# Tracker_RS232_2.net
KiCad netlist of a schematic drawn in Altium Designer
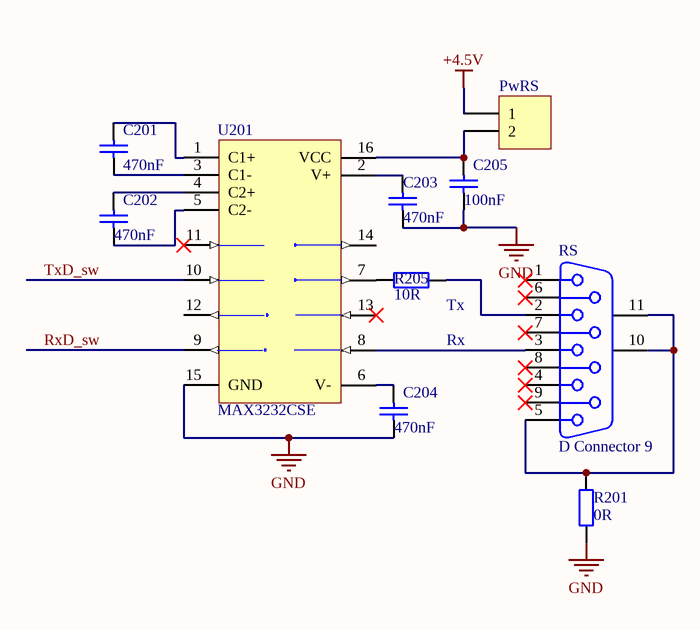
[diagram p0: Tracker RS232_2.SchDoc]

(export (version "E")
  (design (tool "Eeschema 10.0.6"))
  (components
    (comp (ref "C201")
      (value "470nF")
      (footprint "2012[0805]")
      (description "Capacitor (Semiconductor SIM Model)")
      (fields (field (name "Comment") "Cap Semi") (field (name "PUBLISHER") "Altium Limited"))
      (libsource (lib "Miscellaneous Devices") (part "Cap Semi"))
    )
    (comp (ref "C202")
      (value "470nF")
      (footprint "2012[0805]")
      (description "Capacitor (Semiconductor SIM Model)")
      (fields (field (name "Comment") "Cap Semi") (field (name "PUBLISHER") "Altium Limited"))
      (libsource (lib "Miscellaneous Devices") (part "Cap Semi"))
    )
    (comp (ref "C203")
      (value "470nF")
      (footprint "2012[0805]")
      (description "Capacitor (Semiconductor SIM Model)")
      (fields (field (name "Comment") "Cap Semi") (field (name "PUBLISHER") "Altium Limited"))
      (libsource (lib "Miscellaneous Devices") (part "Cap Semi"))
    )
    (comp (ref "C204")
      (value "470nF")
      (footprint "2012[0805]")
      (description "Capacitor (Semiconductor SIM Model)")
      (fields (field (name "Comment") "Cap Semi") (field (name "PUBLISHER") "Altium Limited"))
      (libsource (lib "Miscellaneous Devices") (part "Cap Semi"))
    )
    (comp (ref "C205")
      (value "100nF")
      (footprint "2012[0805]")
      (description "Capacitor (Semiconductor SIM Model)")
      (fields (field (name "Comment") "Cap Semi") (field (name "PUBLISHER") "Altium Limited"))
      (libsource (lib "Miscellaneous Devices") (part "Cap Semi"))
    )
    (comp (ref "PwRS")
      (value "Header 2")
      (footprint "HDR1X2")
      (description "Header, 2-Pin")
      (fields (field (name "PUBLISHER") "Altium Limited"))
      (libsource (lib "Miscellaneous Connectors") (part "Header 2"))
    )
    (comp (ref "R201")
      (value "0R")
      (footprint "3216[1206]")
      (description "Resistor")
      (fields (field (name "Comment") "Res2") (field (name "PUBLISHER") "Altium Limited"))
      (libsource (lib "") (part "Res2_1"))
    )
    (comp (ref "R205")
      (value "10R")
      (footprint "2012[0805]")
      (description "Resistor")
      (fields (field (name "Comment") "Res2") (field (name "PUBLISHER") "Altium Limited"))
      (libsource (lib "Miscellaneous Devices") (part "Res2"))
    )
    (comp (ref "RS")
      (value "D Connector 9")
      (footprint "DSUB1.385-2H9")
      (description "Receptacle Assembly, 9 Position, Right Angle")
      (fields (field (name "PUBLISHER") "Altium Limited"))
      (libsource (lib "Miscellaneous Connectors") (part "D Connector 9"))
    )
    (comp (ref "U201")
      (value "MAX3232CSE")
      (footprint "NSO16_N")
      (description "3.0V TO 5.5V, Low-Power, up to 1Mbps, True RS-232 Transceiver Using Four 0.1µF External Capacitor")
      (fields (field (name "PUBLISHER") "Altium Limited"))
      (libsource (lib "Maxim Communication Transceiver") (part "MAX3232CSE"))
    )
  )
  (nets
    (net (code "1") (name "+4.5V") (class "Default")
      (node (ref "PwRS") (pin "1") (pinfunction "1_1") (pintype "passive"))
    )
    (net (code "2") (name "/RxD_sw") (class "Default")
      (node (ref "U201") (pin "9") (pinfunction "R2OUT_9") (pintype "output"))
    )
    (net (code "3") (name "/TxD_sw") (class "Default")
      (node (ref "U201") (pin "10") (pinfunction "T2IN_10") (pintype "input"))
    )
    (net (code "4") (name "GND") (class "Default")
      (node (ref "C203") (pin "1") (pinfunction "1_1") (pintype "passive"))
      (node (ref "C204") (pin "1") (pinfunction "1_1") (pintype "passive"))
      (node (ref "C205") (pin "1") (pinfunction "1_1") (pintype "passive"))
      (node (ref "R201") (pin "2") (pinfunction "2_2") (pintype "passive"))
      (node (ref "U201") (pin "15") (pinfunction "GND_15") (pintype "power_in"))
    )
    (net (code "5") (name "Net-(R205-Pad2)") (class "Default")
      (node (ref "R205") (pin "2") (pinfunction "2_2") (pintype "passive"))
      (node (ref "RS") (pin "2") (pinfunction "2_2") (pintype "passive"))
    )
    (net (code "6") (name "Net-(RS-MH1)") (class "Default")
      (node (ref "R201") (pin "1") (pinfunction "1_1") (pintype "passive"))
      (node (ref "RS") (pin "10") (pinfunction "MH1_10") (pintype "passive"))
      (node (ref "RS") (pin "11") (pinfunction "MH2_11") (pintype "passive"))
      (node (ref "RS") (pin "5") (pinfunction "5_5") (pintype "passive"))
    )
    (net (code "7") (name "Net-(U201-C1+)") (class "Default")
      (node (ref "C201") (pin "2") (pinfunction "2_2") (pintype "passive"))
      (node (ref "U201") (pin "1") (pinfunction "C1+_1") (pintype "passive"))
    )
    (net (code "8") (name "Net-(U201-C1-)") (class "Default")
      (node (ref "C201") (pin "1") (pinfunction "1_1") (pintype "passive"))
      (node (ref "U201") (pin "3") (pinfunction "C1-_3") (pintype "passive"))
    )
    (net (code "9") (name "Net-(U201-C2+)") (class "Default")
      (node (ref "C202") (pin "2") (pinfunction "2_2") (pintype "passive"))
      (node (ref "U201") (pin "4") (pinfunction "C2+_4") (pintype "passive"))
    )
    (net (code "10") (name "Net-(U201-C2-)") (class "Default")
      (node (ref "C202") (pin "1") (pinfunction "1_1") (pintype "passive"))
      (node (ref "U201") (pin "5") (pinfunction "C2-_5") (pintype "passive"))
    )
    (net (code "11") (name "Net-(U201-R2IN)") (class "Default")
      (node (ref "RS") (pin "3") (pinfunction "3_3") (pintype "passive"))
      (node (ref "U201") (pin "8") (pinfunction "R2IN_8") (pintype "input"))
    )
    (net (code "12") (name "Net-(U201-T2OUT)") (class "Default")
      (node (ref "R205") (pin "1") (pinfunction "1_1") (pintype "passive"))
      (node (ref "U201") (pin "7") (pinfunction "T2OUT_7") (pintype "output"))
    )
    (net (code "13") (name "Net-(U201-V+)") (class "Default")
      (node (ref "C203") (pin "2") (pinfunction "2_2") (pintype "passive"))
      (node (ref "U201") (pin "2") (pinfunction "V+_2") (pintype "power_in"))
    )
    (net (code "14") (name "Net-(U201-V-)") (class "Default")
      (node (ref "C204") (pin "2") (pinfunction "2_2") (pintype "passive"))
      (node (ref "U201") (pin "6") (pinfunction "V-_6") (pintype "power_in"))
    )
    (net (code "15") (name "Net-(U201-VCC)") (class "Default")
      (node (ref "C205") (pin "2") (pinfunction "2_2") (pintype "passive"))
      (node (ref "PwRS") (pin "2") (pinfunction "2_2") (pintype "passive"))
      (node (ref "U201") (pin "16") (pinfunction "VCC_16") (pintype "power_in"))
    )
    (net (code "16") (name "unconnected-(RS-Pad1)") (class "Default")
      (node (ref "RS") (pin "1") (pinfunction "1_1") (pintype "passive+no_connect"))
    )
    (net (code "17") (name "unconnected-(RS-Pad4)") (class "Default")
      (node (ref "RS") (pin "4") (pinfunction "4_4") (pintype "passive+no_connect"))
    )
    (net (code "18") (name "unconnected-(RS-Pad6)") (class "Default")
      (node (ref "RS") (pin "6") (pinfunction "6_6") (pintype "passive+no_connect"))
    )
    (net (code "19") (name "unconnected-(RS-Pad7)") (class "Default")
      (node (ref "RS") (pin "7") (pinfunction "7_7") (pintype "passive+no_connect"))
    )
    (net (code "20") (name "unconnected-(RS-Pad8)") (class "Default")
      (node (ref "RS") (pin "8") (pinfunction "8_8") (pintype "passive+no_connect"))
    )
    (net (code "21") (name "unconnected-(RS-Pad9)") (class "Default")
      (node (ref "RS") (pin "9") (pinfunction "9_9") (pintype "passive+no_connect"))
    )
    (net (code "22") (name "unconnected-(U201-R1IN-Pad13)") (class "Default")
      (node (ref "U201") (pin "13") (pinfunction "R1IN_13") (pintype "input+no_connect"))
    )
    (net (code "23") (name "unconnected-(U201-R1OUT-Pad12)") (class "Default")
      (node (ref "U201") (pin "12") (pinfunction "R1OUT_12") (pintype "output"))
    )
    (net (code "24") (name "unconnected-(U201-T1IN-Pad11)") (class "Default")
      (node (ref "U201") (pin "11") (pinfunction "T1IN_11") (pintype "input+no_connect"))
    )
    (net (code "25") (name "unconnected-(U201-T1OUT-Pad14)") (class "Default")
      (node (ref "U201") (pin "14") (pinfunction "T1OUT_14") (pintype "output"))
    )
  )
)
